# esp8266.net
KiCad netlist of a schematic drawn in EAGLE
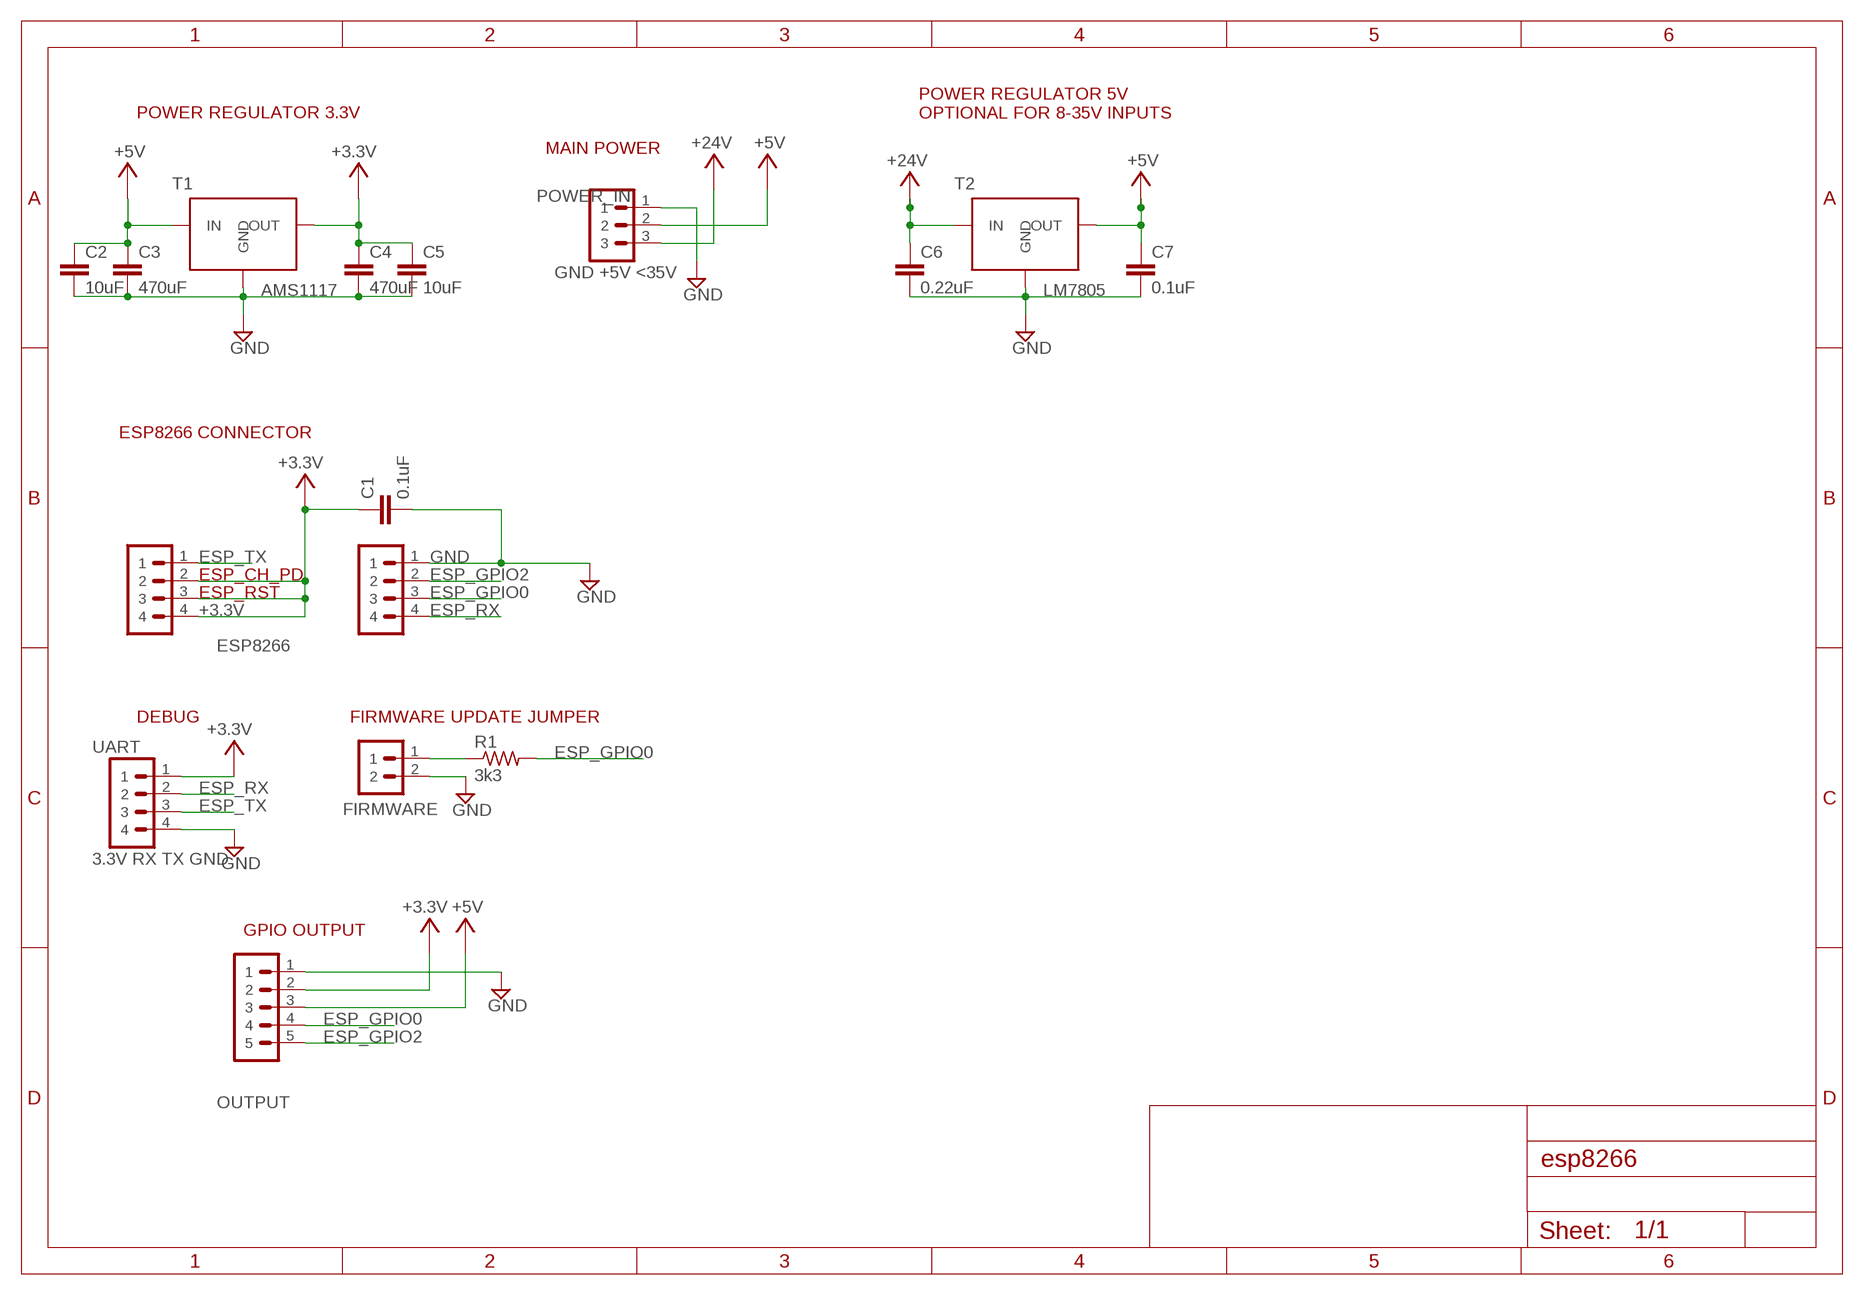
[diagram p0: schematic, sheet 1]

(export (version "E")
  (design (tool "Eeschema 10.0.6"))
  (components
    (comp (ref "C1")
      (value "0.1uF")
      (footprint "eagle-import:C2.5-2")
      (libsource (lib "eagle-import") (part "C2.5/2"))
    )
    (comp (ref "C2")
      (value "10uF")
      (footprint "eagle-import:C2.5-2")
      (libsource (lib "eagle-import") (part "C2.5/2"))
    )
    (comp (ref "C3")
      (value "470uF")
      (footprint "eagle-import:C2.5-2")
      (fields (field (name "MPN") "1C10Z5U104M050B"))
      (libsource (lib "eagle-import") (part "C2.5/2"))
    )
    (comp (ref "C4")
      (value "470uF")
      (footprint "eagle-import:C2.5-2")
      (fields (field (name "MPN") "FK18X5R0J106M"))
      (libsource (lib "eagle-import") (part "C2.5/2"))
    )
    (comp (ref "C5")
      (value "10uF")
      (footprint "eagle-import:C2.5-2")
      (libsource (lib "eagle-import") (part "C2.5/2"))
    )
    (comp (ref "C6")
      (value "0.22uF")
      (footprint "eagle-import:C2.5-2")
      (fields (field (name "MPN") "1C10Z5U104M050B"))
      (libsource (lib "eagle-import") (part "C2.5/2"))
    )
    (comp (ref "C7")
      (value "0.1uF")
      (footprint "eagle-import:C2.5-2")
      (fields (field (name "MPN") "FK18X5R0J106M"))
      (libsource (lib "eagle-import") (part "C2.5/2"))
    )
    (comp (ref "FIRMWARE")
      (value "FIRMWARE")
      (footprint "eagle-import:PIN-HEADER-2PIN")
      (libsource (lib "eagle-import") (part "PIN-HEADER-2PIN"))
    )
    (comp (ref "OUTPUT")
      (value "GND 3.3V 5V IO0 IO2")
      (footprint "eagle-import:PIN-HEADER-5PIN")
      (libsource (lib "eagle-import") (part "PIN-HEADER-5PIN"))
    )
    (comp (ref "P1")
      (value "ESP8266")
      (footprint "eagle-import:PIN-HEADER-4PIN")
      (libsource (lib "eagle-import") (part "PIN-HEADER-4PIN"))
    )
    (comp (ref "P2")
      (value "ESP8266 CONNECTOR")
      (footprint "eagle-import:PIN-HEADER-4PIN")
      (libsource (lib "eagle-import") (part "PIN-HEADER-4PIN"))
    )
    (comp (ref "POWER_IN")
      (value "GND +5V <35V")
      (footprint "eagle-import:PIN-HEADER-3PIN")
      (libsource (lib "eagle-import") (part "PIN-HEADER-3PIN"))
    )
    (comp (ref "R1")
      (value "3k3")
      (footprint "eagle-import:RESISTOR-V3")
      (libsource (lib "eagle-import") (part "RESISTORV3"))
    )
    (comp (ref "T1")
      (value "AMS1117")
      (footprint "eagle-import:SOT-223")
      (fields (field (name "MPN") "LM2937ET-3.3"))
      (libsource (lib "eagle-import") (part "AMS1117"))
    )
    (comp (ref "T2")
      (value "LM7805")
      (footprint "eagle-import:TO-220")
      (fields (field (name "MPN") "LM2937ET-3.3"))
      (libsource (lib "eagle-import") (part "LM7805"))
    )
    (comp (ref "UART")
      (value "3.3V RX TX GND")
      (footprint "eagle-import:PIN-HEADER-4PIN")
      (libsource (lib "eagle-import") (part "PIN-HEADER-4PIN"))
    )
  )
  (nets
    (net (code "1") (name "+3.3V") (class "Default")
      (node (ref "C1") (pin "1") (pinfunction "1_1") (pintype "passive"))
      (node (ref "C4") (pin "1") (pinfunction "1_1") (pintype "passive"))
      (node (ref "C5") (pin "1") (pinfunction "1_1") (pintype "passive"))
      (node (ref "OUTPUT") (pin "2") (pinfunction "2_2") (pintype "passive"))
      (node (ref "P1") (pin "2") (pinfunction "2_2") (pintype "passive"))
      (node (ref "P1") (pin "3") (pinfunction "3_3") (pintype "passive"))
      (node (ref "P1") (pin "4") (pinfunction "4_4") (pintype "passive"))
      (node (ref "T1") (pin "2") (pinfunction "OUT_2") (pintype "power_in"))
      (node (ref "UART") (pin "1") (pinfunction "1_1") (pintype "passive"))
    )
    (net (code "2") (name "+5V") (class "Default")
      (node (ref "C2") (pin "1") (pinfunction "1_1") (pintype "passive"))
      (node (ref "C3") (pin "1") (pinfunction "1_1") (pintype "passive"))
      (node (ref "C7") (pin "1") (pinfunction "1_1") (pintype "passive"))
      (node (ref "OUTPUT") (pin "3") (pinfunction "3_3") (pintype "passive"))
      (node (ref "POWER_IN") (pin "2") (pinfunction "2_2") (pintype "passive"))
      (node (ref "T1") (pin "3") (pinfunction "IN_3") (pintype "power_in"))
      (node (ref "T2") (pin "OUTPUT") (pinfunction "OUT_OUTPUT") (pintype "power_in"))
    )
    (net (code "3") (name "+24V") (class "Default")
      (node (ref "C6") (pin "1") (pinfunction "1_1") (pintype "passive"))
      (node (ref "POWER_IN") (pin "3") (pinfunction "3_3") (pintype "passive"))
      (node (ref "T2") (pin "INPUT") (pinfunction "IN_INPUT") (pintype "power_in"))
    )
    (net (code "4") (name "/ESP_GPIO0") (class "Default")
      (node (ref "OUTPUT") (pin "4") (pinfunction "4_4") (pintype "passive"))
      (node (ref "P2") (pin "3") (pinfunction "3_3") (pintype "passive"))
      (node (ref "R1") (pin "2") (pinfunction "2_2") (pintype "passive"))
    )
    (net (code "5") (name "/ESP_GPIO2") (class "Default")
      (node (ref "OUTPUT") (pin "5") (pinfunction "5_5") (pintype "passive"))
      (node (ref "P2") (pin "2") (pinfunction "2_2") (pintype "passive"))
    )
    (net (code "6") (name "/ESP_RX") (class "Default")
      (node (ref "P2") (pin "4") (pinfunction "4_4") (pintype "passive"))
      (node (ref "UART") (pin "2") (pinfunction "2_2") (pintype "passive"))
    )
    (net (code "7") (name "/ESP_TX") (class "Default")
      (node (ref "P1") (pin "1") (pinfunction "1_1") (pintype "passive"))
      (node (ref "UART") (pin "3") (pinfunction "3_3") (pintype "passive"))
    )
    (net (code "8") (name "GND") (class "Default")
      (node (ref "C1") (pin "2") (pinfunction "2_2") (pintype "passive"))
      (node (ref "C2") (pin "2") (pinfunction "2_2") (pintype "passive"))
      (node (ref "C3") (pin "2") (pinfunction "2_2") (pintype "passive"))
      (node (ref "C4") (pin "2") (pinfunction "2_2") (pintype "passive"))
      (node (ref "C5") (pin "2") (pinfunction "2_2") (pintype "passive"))
      (node (ref "C6") (pin "2") (pinfunction "2_2") (pintype "passive"))
      (node (ref "C7") (pin "2") (pinfunction "2_2") (pintype "passive"))
      (node (ref "FIRMWARE") (pin "2") (pinfunction "2_2") (pintype "passive"))
      (node (ref "OUTPUT") (pin "1") (pinfunction "1_1") (pintype "passive"))
      (node (ref "P2") (pin "1") (pinfunction "1_1") (pintype "passive"))
      (node (ref "POWER_IN") (pin "1") (pinfunction "1_1") (pintype "passive"))
      (node (ref "T1") (pin "1") (pinfunction "GND_1") (pintype "power_in"))
      (node (ref "T2") (pin "GND") (pinfunction "GND_GND") (pintype "power_in"))
      (node (ref "UART") (pin "4") (pinfunction "4_4") (pintype "passive"))
    )
    (net (code "9") (name "Net-(FIRMWARE-Pad1)") (class "Default")
      (node (ref "FIRMWARE") (pin "1") (pinfunction "1_1") (pintype "passive"))
      (node (ref "R1") (pin "1") (pinfunction "1_1") (pintype "passive"))
    )
  )
)
